# Communication.net
KiCad netlist of a schematic drawn in Altium Designer
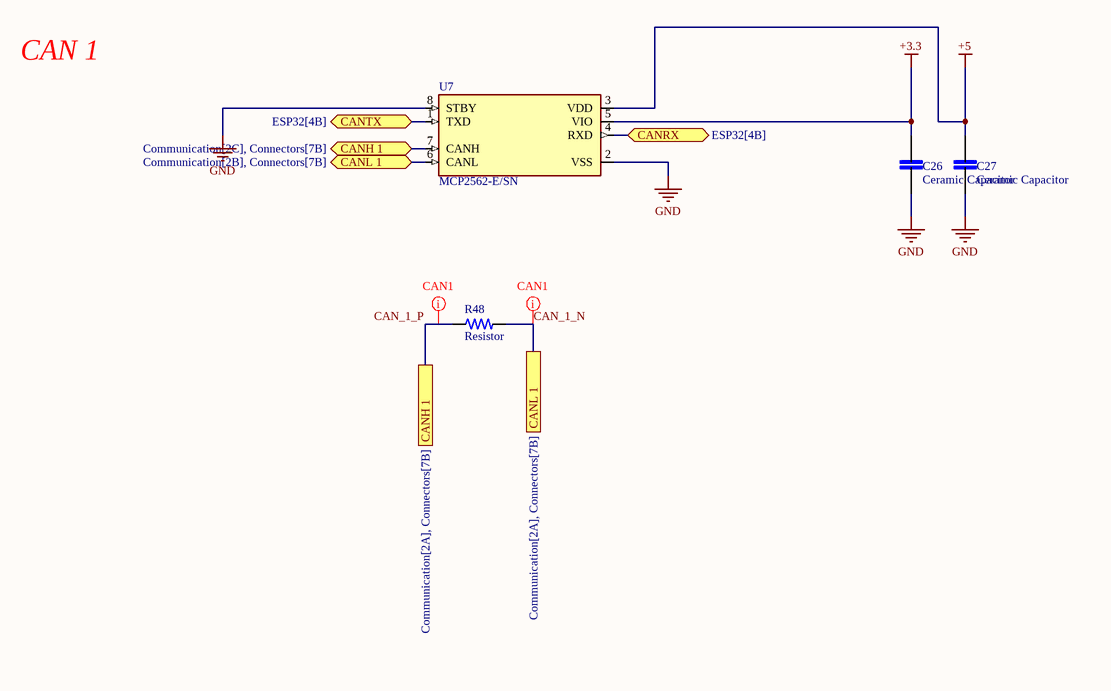
[diagram p0: Communication.SchDoc]

(export (version "E")
  (design (tool "Eeschema 10.0.6"))
  (components
    (comp (ref "C26")
      (value "Ceramic Capacitor")
      (footprint "Ceramic Capacitor")
      (fields (field (name "MP") "LD051A121KAB2A") (field (name "MF") "AVX"))
      (libsource (lib "Capacitors Through Hole") (part "Ceramic Capacitor"))
    )
    (comp (ref "C27")
      (value "Ceramic Capacitor")
      (footprint "Ceramic Capacitor")
      (fields (field (name "MP") "LD051A121KAB2A") (field (name "MF") "AVX"))
      (libsource (lib "Capacitors Through Hole") (part "Ceramic Capacitor"))
    )
    (comp (ref "R48")
      (value "Resistor")
      (footprint "Resistor_Through Hole")
      (fields
        (field (name "MP") "2-2176053-0")
        (field (name "TOLERANCE") "1%")
        (field (name "MF") "TE Connectivity")
      )
      (libsource (lib "Resistors Through Hole") (part "Resistor"))
    )
    (comp (ref "U7")
      (value "MCP2562-E/SN")
      (footprint "Transceiver CAN:MCP2562-E/SN")
      (description "1/1 Transceiver Half CANbus 8-SOIC")
      (fields (field (name "MF") "Microchip"))
      (libsource (lib "Transceiver CAN") (part "MCP2562-E/SN"))
    )
  )
  (nets
    (net (code "1") (name "+3.3") (class "Default")
      (node (ref "C26") (pin "2") (pinfunction "2_2") (pintype "passive"))
      (node (ref "U7") (pin "5") (pinfunction "VIO_5") (pintype "power_in"))
    )
    (net (code "2") (name "+5") (class "Default")
      (node (ref "C27") (pin "2") (pinfunction "2_2") (pintype "passive"))
      (node (ref "U7") (pin "3") (pinfunction "VDD_3") (pintype "power_in"))
    )
    (net (code "3") (name "/CANRX") (class "Default")
      (node (ref "U7") (pin "4") (pinfunction "RXD_4") (pintype "output"))
    )
    (net (code "4") (name "/CANTX") (class "Default")
      (node (ref "U7") (pin "1") (pinfunction "TXD_1") (pintype "input"))
    )
    (net (code "5") (name "/CAN_1_N") (class "Default")
      (node (ref "R48") (pin "2") (pinfunction "2_2") (pintype "passive"))
      (node (ref "U7") (pin "6") (pinfunction "CANL_6") (pintype "input"))
    )
    (net (code "6") (name "/CAN_1_P") (class "Default")
      (node (ref "R48") (pin "1") (pinfunction "1_1") (pintype "passive"))
      (node (ref "U7") (pin "7") (pinfunction "CANH_7") (pintype "input"))
    )
    (net (code "7") (name "GND") (class "Default")
      (node (ref "C26") (pin "1") (pinfunction "1_1") (pintype "passive"))
      (node (ref "C27") (pin "1") (pinfunction "1_1") (pintype "passive"))
      (node (ref "U7") (pin "2") (pinfunction "VSS_2") (pintype "power_in"))
      (node (ref "U7") (pin "8") (pinfunction "STBY_8") (pintype "input"))
    )
  )
)
